# HEBreakoutrev2.net
KiCad netlist of a schematic drawn in EAGLE
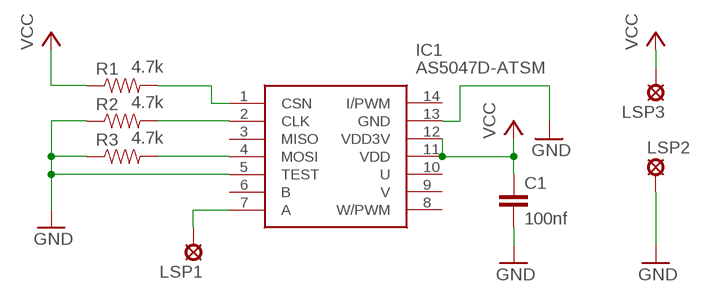
[diagram p0: schematic, sheet 1]

(export (version "E")
  (design (tool "Eeschema 10.0.6"))
  (components
    (comp (ref "C1")
      (value "100nf")
      (footprint "eagle-import:0603-CAP")
      (libsource (lib "eagle-import") (part "CAP0603-CAP"))
    )
    (comp (ref "IC1")
      (value "AS5047D-ATSM")
      (footprint "eagle-import:SOP65P640X120-14N")
      (fields (field (name "MOUSER_PART_NUMBER") "985-AS5047D-ATSM"))
      (libsource (lib "eagle-import") (part "AS5047D-ATSM"))
    )
    (comp (ref "LSP1")
      (value "LSP10")
      (footprint "eagle-import:LSP10")
      (libsource (lib "eagle-import") (part "LSP10"))
    )
    (comp (ref "LSP2")
      (value "LSP10")
      (footprint "eagle-import:LSP10")
      (libsource (lib "eagle-import") (part "LSP10"))
    )
    (comp (ref "LSP3")
      (value "LSP10")
      (footprint "eagle-import:LSP10")
      (libsource (lib "eagle-import") (part "LSP10"))
    )
    (comp (ref "R1")
      (value "4.7k")
      (footprint "eagle-import:0603-RES")
      (libsource (lib "eagle-import") (part "RESISTOR0603"))
    )
    (comp (ref "R2")
      (value "4.7k")
      (footprint "eagle-import:0603-RES")
      (libsource (lib "eagle-import") (part "RESISTOR0603"))
    )
    (comp (ref "R3")
      (value "4.7k")
      (footprint "eagle-import:0603-RES")
      (libsource (lib "eagle-import") (part "RESISTOR0603"))
    )
  )
  (nets
    (net (code "1") (name "GND") (class "Default")
      (node (ref "C1") (pin "2") (pinfunction "2_2") (pintype "passive"))
      (node (ref "IC1") (pin "13") (pinfunction "GND_13") (pintype "bidirectional"))
      (node (ref "IC1") (pin "5") (pinfunction "TEST_5") (pintype "bidirectional"))
      (node (ref "LSP2") (pin "MP") (pinfunction "MP_MP") (pintype "passive"))
      (node (ref "R2") (pin "1") (pinfunction "1_1") (pintype "passive"))
      (node (ref "R3") (pin "1") (pinfunction "1_1") (pintype "passive"))
    )
    (net (code "2") (name "Net-(IC1-A)") (class "Default")
      (node (ref "IC1") (pin "7") (pinfunction "A_7") (pintype "bidirectional"))
      (node (ref "LSP1") (pin "MP") (pinfunction "MP_MP") (pintype "passive"))
    )
    (net (code "3") (name "Net-(IC1-CLK)") (class "Default")
      (node (ref "IC1") (pin "2") (pinfunction "CLK_2") (pintype "bidirectional"))
      (node (ref "R2") (pin "2") (pinfunction "2_2") (pintype "passive"))
    )
    (net (code "4") (name "Net-(IC1-CSN)") (class "Default")
      (node (ref "IC1") (pin "1") (pinfunction "CSN_1") (pintype "bidirectional"))
      (node (ref "R1") (pin "2") (pinfunction "2_2") (pintype "passive"))
    )
    (net (code "5") (name "Net-(IC1-MOSI)") (class "Default")
      (node (ref "IC1") (pin "4") (pinfunction "MOSI_4") (pintype "bidirectional"))
      (node (ref "R3") (pin "2") (pinfunction "2_2") (pintype "passive"))
    )
    (net (code "6") (name "VCC") (class "Default")
      (node (ref "C1") (pin "1") (pinfunction "1_1") (pintype "passive"))
      (node (ref "IC1") (pin "11") (pinfunction "VDD_11") (pintype "bidirectional"))
      (node (ref "IC1") (pin "12") (pinfunction "VDD3V_12") (pintype "bidirectional"))
      (node (ref "LSP3") (pin "MP") (pinfunction "MP_MP") (pintype "passive"))
      (node (ref "R1") (pin "1") (pinfunction "1_1") (pintype "passive"))
    )
    (net (code "7") (name "unconnected-(IC1-B-Pad6)") (class "Default")
      (node (ref "IC1") (pin "6") (pinfunction "B_6") (pintype "bidirectional"))
    )
    (net (code "8") (name "unconnected-(IC1-I{slash}PWM-Pad14)") (class "Default")
      (node (ref "IC1") (pin "14") (pinfunction "I/PWM_14") (pintype "bidirectional"))
    )
    (net (code "9") (name "unconnected-(IC1-MISO-Pad3)") (class "Default")
      (node (ref "IC1") (pin "3") (pinfunction "MISO_3") (pintype "bidirectional"))
    )
    (net (code "10") (name "unconnected-(IC1-U-Pad10)") (class "Default")
      (node (ref "IC1") (pin "10") (pinfunction "U_10") (pintype "bidirectional"))
    )
    (net (code "11") (name "unconnected-(IC1-V-Pad9)") (class "Default")
      (node (ref "IC1") (pin "9") (pinfunction "V_9") (pintype "bidirectional"))
    )
    (net (code "12") (name "unconnected-(IC1-W{slash}PWM-Pad8)") (class "Default")
      (node (ref "IC1") (pin "8") (pinfunction "W/PWM_8") (pintype "bidirectional"))
    )
  )
)
